# Sheet1.net
KiCad netlist of a schematic drawn in Altium Designer
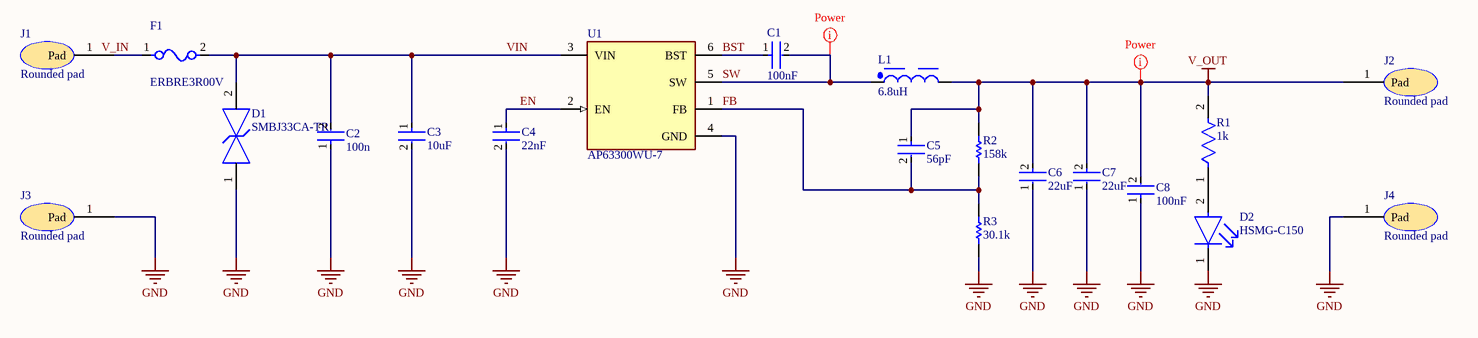
[diagram p0: Sheet1.SchDoc]

(export (version "E")
  (design (tool "Eeschema 10.0.6"))
  (components
    (comp (ref "C1")
      (value "100nF")
      (footprint "FP-CGA3E-0_3-0_1-IPC_A")
      (description "Cap Ceramic 100nF 50V X7R 10% Pad SMD 0603 +125°C Automotive T/R")
      (fields (field (name "TOLERANCE") "10%") (field (name "VOLTAGE") "50V"))
      (libsource (lib "Altium Content Vault") (part "b4654b650e69147ec39a6b967a45e02"))
    )
    (comp (ref "C2")
      (value "100n")
      (footprint "FP-CGA3E-0_3-0_1-IPC_A")
      (description "Cap Ceramic 100nF 50V X7R 10% Pad SMD 0603 +125°C Automotive T/R")
      (fields (field (name "TOLERANCE") "10%") (field (name "VOLTAGE") "50V"))
      (libsource (lib "Altium Content Vault") (part "b4654b650e69147ec39a6b967a45e02"))
    )
    (comp (ref "C3")
      (value "10uF")
      (footprint "FP-2220-L_5_7_0_5-W_5_0_4-IPC_A")
      (description "General Purpose Ceramic Capacitor, 2220, 10uF, 10%, X7R, 15%, 50V")
      (fields (field (name "TOLERANCE") "10%") (field (name "VOLTAGE") "50V"))
      (libsource (lib "Altium Content Vault") (part "02cd4be3c70576c341d710602a673aa"))
    )
    (comp (ref "C4")
      (value "22nF")
      (footprint "FP-CC0603-DA-MFG")
      (description "CAP CER 0.022UF 50V X7R 0603")
      (fields (field (name "TOLERANCE") "10%") (field (name "VOLTAGE") "50V"))
      (libsource (lib "Altium Content Vault") (part "11868f565c42a9108669ba33697ecf6"))
    )
    (comp (ref "C5")
      (value "56pF")
      (footprint "FP-C0603C-CF-MFG")
      (description "CAP CER 56PF 50V 1% NP0 0603")
      (fields (field (name "TOLERANCE") "0.01") (field (name "MANUFACTURER") "KEMET"))
      (libsource (lib "Altium Content Vault") (part "b4654b650e69147ec39a6b967a45e02"))
    )
    (comp (ref "C6")
      (value "22uF")
      (footprint "FP-GCM32E-0_35-e0_3_1_275-MFG")
      (description "Ceramic Capacitor for Automotive 22uF ±10% 25VDC X8L 1210 Embossed T/R")
      (libsource (lib "Altium Content Vault") (part "f23184f103b6ebe33a8c269c53dcba6"))
    )
    (comp (ref "C7")
      (value "22uF")
      (footprint "FP-GCM32E-0_35-e0_3_1_275-MFG")
      (description "Ceramic Capacitor for Automotive 22uF ±10% 25VDC X8L 1210 Embossed T/R")
      (libsource (lib "Altium Content Vault") (part "f23184f103b6ebe33a8c269c53dcba6"))
    )
    (comp (ref "C8")
      (value "100nF")
      (footprint "FP-CGA3E-0_3-0_1-IPC_A")
      (description "Cap Ceramic 100nF 50V X7R 10% Pad SMD 0603 +125°C Automotive T/R")
      (fields (field (name "TOLERANCE") "10%") (field (name "VOLTAGE") "50V"))
      (libsource (lib "Altium Content Vault") (part "b4654b650e69147ec39a6b967a45e02"))
    )
    (comp (ref "D1")
      (value "SMBJ33CA-TR")
      (footprint "FP-SMB-CA-MFG")
      (description "TVS DIODE 33V 69.7V SMB")
      (fields
        (field (name "OCTOPART") "https://octopart.com/smbj33ca-tr-stmicroelectronics-347069")
        (field (name "MANUFACTURER") "STMicroelectronics")
      )
      (libsource (lib "Altium Content Vault") (part "11bd9d59d340f0612179daf16ad9b72"))
    )
    (comp (ref "D2")
      (value "HSMG-C150")
      (footprint "FP-HSMG-C150-MFG")
      (description "LED GREEN DIFFUSED 1206 SMD")
      (fields
        (field (name "MANUFACTURER") "Broadcom")
        (field (name "OCTOPART") "https://octopart.com/hsmg-c150-broadcom-71131304")
      )
      (libsource (lib "Altium Content Vault") (part "8706943c75ba83719d021d2fdc84c58"))
    )
    (comp (ref "F1")
      (value "ERBRE3R00V")
      (footprint "FP-ERBRE-MFG")
      (description "ERBRE3R00V Fuse Chip Fast Acting 3A 32V SMD Solder Pad 0603 1.6 X 0.8 X 0.54mm T/R UL/cUL")
      (libsource (lib "Altium Content Vault") (part "ERBRE3R00V"))
    )
    (comp (ref "J1")
      (value "Rounded pad")
      (footprint "PCBComponent_1")
      (libsource (lib "Stepdown") (part "Rounded pad"))
    )
    (comp (ref "J2")
      (value "Rounded pad")
      (footprint "PCBComponent_1")
      (libsource (lib "Stepdown") (part "Rounded pad"))
    )
    (comp (ref "J3")
      (value "Rounded pad")
      (footprint "PCBComponent_1")
      (libsource (lib "Stepdown") (part "Rounded pad"))
    )
    (comp (ref "J4")
      (value "Rounded pad")
      (footprint "PCBComponent_1")
      (libsource (lib "Stepdown") (part "Rounded pad"))
    )
    (comp (ref "L1")
      (value "6.8uH")
      (footprint "WE-LHMI_8030")
      (description "74437356068 Power Inductor, 6.8Uh, Shielded, 5.1A Rohs Compliant: Yes")
      (fields (field (name "TOLERANCE") "20%"))
      (libsource (lib "Altium Content Vault") (part "Inductor - 2"))
    )
    (comp (ref "R1")
      (value "1k")
      (footprint "FP-AC0603-IPC_B")
      (description "RES 1kΩ 1.00% 0.1W 0603")
      (fields (field (name "TOLERANCE") "1%"))
      (libsource (lib "Altium Content Vault") (part "1029c3af85768c4190bb7ad29bc67b5"))
    )
    (comp (ref "R2")
      (value "158k")
      (footprint "RESC1609X50X30LL10T20")
      (fields (field (name "MANUFACTURER") "Vishay Dale") (field (name "PART NUMBER") "CRCW060330K1FKEA"))
      (libsource (lib "Altium Content Vault") (part "RES"))
    )
    (comp (ref "R3")
      (value "30.1k")
      (footprint "RESC1608X55X30NL15T15")
      (fields (field (name "MANUFACTURER") "Panasonic") (field (name "PART NUMBER") "ERJ-3EKF1583V"))
      (libsource (lib "Altium Content Vault") (part "RES"))
    )
    (comp (ref "U1")
      (value "AP63300WU-7")
      (footprint "FP-TSOT26-IPC_A")
      (description "DCDC CONV HV BUCK TSOT26")
      (libsource (lib "Altium Content Vault") (part "1f55634e5cdcb17378ea3938d0fe863"))
    )
  )
  (nets
    (net (code "1") (name "/BST") (class "Default")
      (node (ref "C1") (pin "1") (pinfunction "1_1") (pintype "passive"))
      (node (ref "U1") (pin "6") (pinfunction "BST_6") (pintype "passive"))
    )
    (net (code "2") (name "/EN") (class "Default")
      (node (ref "C4") (pin "1") (pinfunction "1_1") (pintype "passive"))
      (node (ref "U1") (pin "2") (pinfunction "EN_2") (pintype "input"))
    )
    (net (code "3") (name "/FB") (class "Default")
      (node (ref "C5") (pin "2") (pinfunction "2_2") (pintype "passive"))
      (node (ref "R2") (pin "1") (pinfunction "1_1") (pintype "passive"))
      (node (ref "R3") (pin "2") (pinfunction "2_2") (pintype "passive"))
      (node (ref "U1") (pin "1") (pinfunction "FB_1") (pintype "passive"))
    )
    (net (code "4") (name "/SW") (class "Default")
      (node (ref "C1") (pin "2") (pinfunction "2_2") (pintype "passive"))
      (node (ref "L1") (pin "1") (pinfunction "1_1") (pintype "passive"))
      (node (ref "U1") (pin "5") (pinfunction "SW_5") (pintype "passive"))
    )
    (net (code "5") (name "/VIN") (class "Default")
      (node (ref "C2") (pin "2") (pinfunction "2_2") (pintype "passive"))
      (node (ref "C3") (pin "1") (pinfunction "1_1") (pintype "passive"))
      (node (ref "D1") (pin "2") (pinfunction "2_2") (pintype "passive"))
      (node (ref "F1") (pin "2") (pinfunction "2_2") (pintype "passive"))
      (node (ref "U1") (pin "3") (pinfunction "VIN_3") (pintype "power_in"))
    )
    (net (code "7") (name "GND") (class "Default")
      (node (ref "C2") (pin "1") (pinfunction "1_1") (pintype "passive"))
      (node (ref "C3") (pin "2") (pinfunction "2_2") (pintype "passive"))
      (node (ref "C4") (pin "2") (pinfunction "2_2") (pintype "passive"))
      (node (ref "C6") (pin "1") (pinfunction "1_1") (pintype "passive"))
      (node (ref "C7") (pin "1") (pinfunction "1_1") (pintype "passive"))
      (node (ref "C8") (pin "1") (pinfunction "1_1") (pintype "passive"))
      (node (ref "D1") (pin "1") (pinfunction "1_1") (pintype "passive"))
      (node (ref "D2") (pin "1") (pinfunction "C_1") (pintype "passive"))
      (node (ref "J3") (pin "1") (pinfunction "Pad_1") (pintype "passive"))
      (node (ref "J4") (pin "1") (pinfunction "Pad_1") (pintype "passive"))
      (node (ref "R3") (pin "1") (pinfunction "1_1") (pintype "passive"))
      (node (ref "U1") (pin "4") (pinfunction "GND_4") (pintype "power_in"))
    )
    (net (code "8") (name "Net-(D2-A)") (class "Default")
      (node (ref "D2") (pin "2") (pinfunction "A_2") (pintype "passive"))
      (node (ref "R1") (pin "1") (pinfunction "1_1") (pintype "passive"))
    )
    (net (code "9") (name "Net-(F1-Pad1)") (class "Default")
      (node (ref "F1") (pin "1") (pinfunction "1_1") (pintype "passive"))
      (node (ref "J1") (pin "1") (pinfunction "Pad_1") (pintype "passive"))
    )
    (net (code "10") (name "V_OUT") (class "Default")
      (node (ref "C5") (pin "1") (pinfunction "1_1") (pintype "passive"))
      (node (ref "C6") (pin "2") (pinfunction "2_2") (pintype "passive"))
      (node (ref "C7") (pin "2") (pinfunction "2_2") (pintype "passive"))
      (node (ref "C8") (pin "2") (pinfunction "2_2") (pintype "passive"))
      (node (ref "J2") (pin "1") (pinfunction "Pad_1") (pintype "passive"))
      (node (ref "L1") (pin "2") (pinfunction "2_2") (pintype "passive"))
      (node (ref "R1") (pin "2") (pinfunction "2_2") (pintype "passive"))
      (node (ref "R2") (pin "2") (pinfunction "2_2") (pintype "passive"))
    )
  )
)
